# bbc_micro.net
KiCad netlist of a schematic drawn in EAGLE
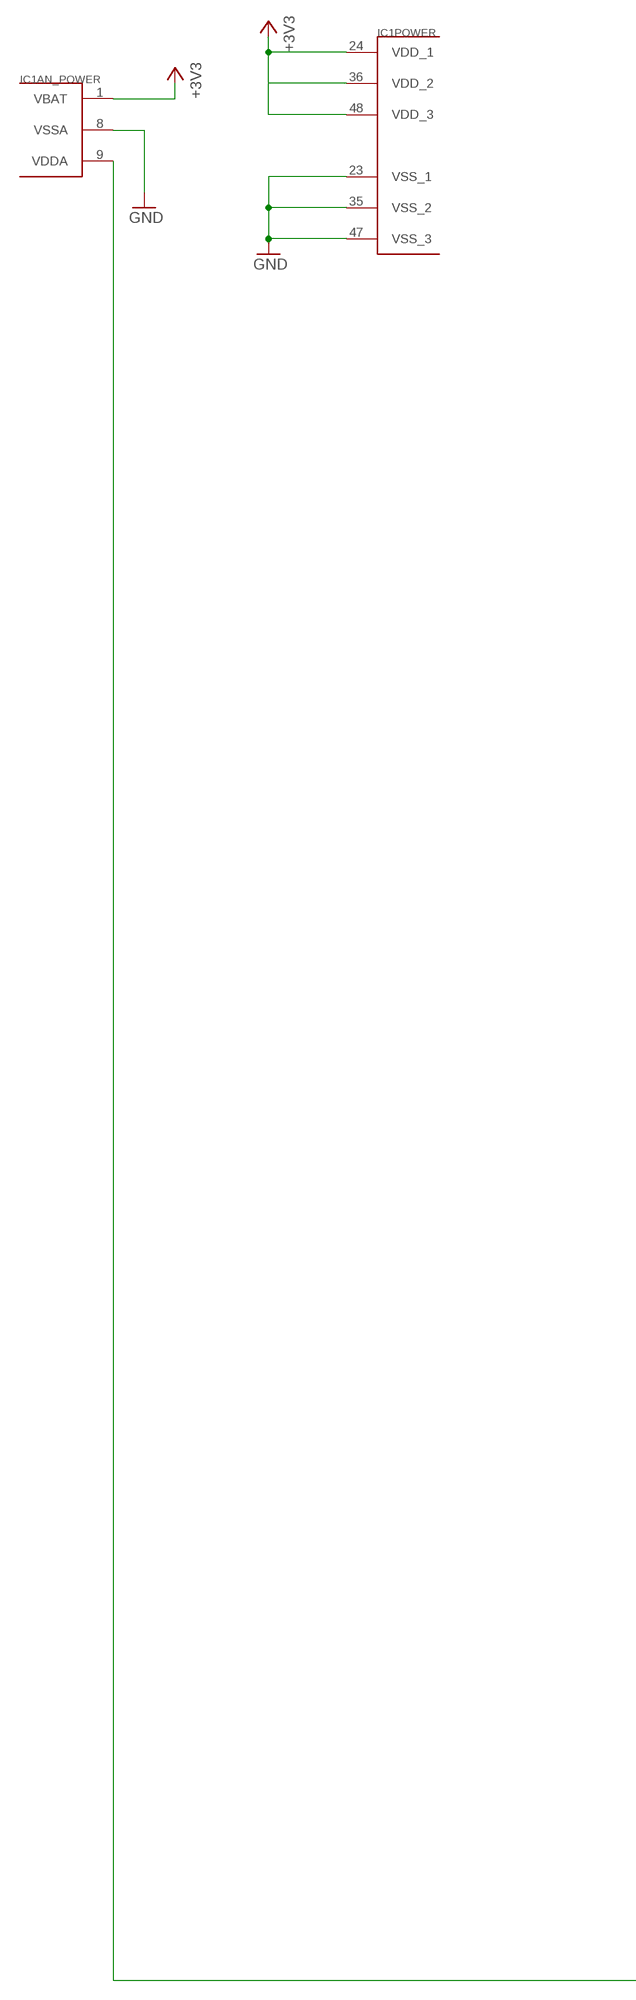
[diagram p0: schematic, sheet 1, part 1 of 2]
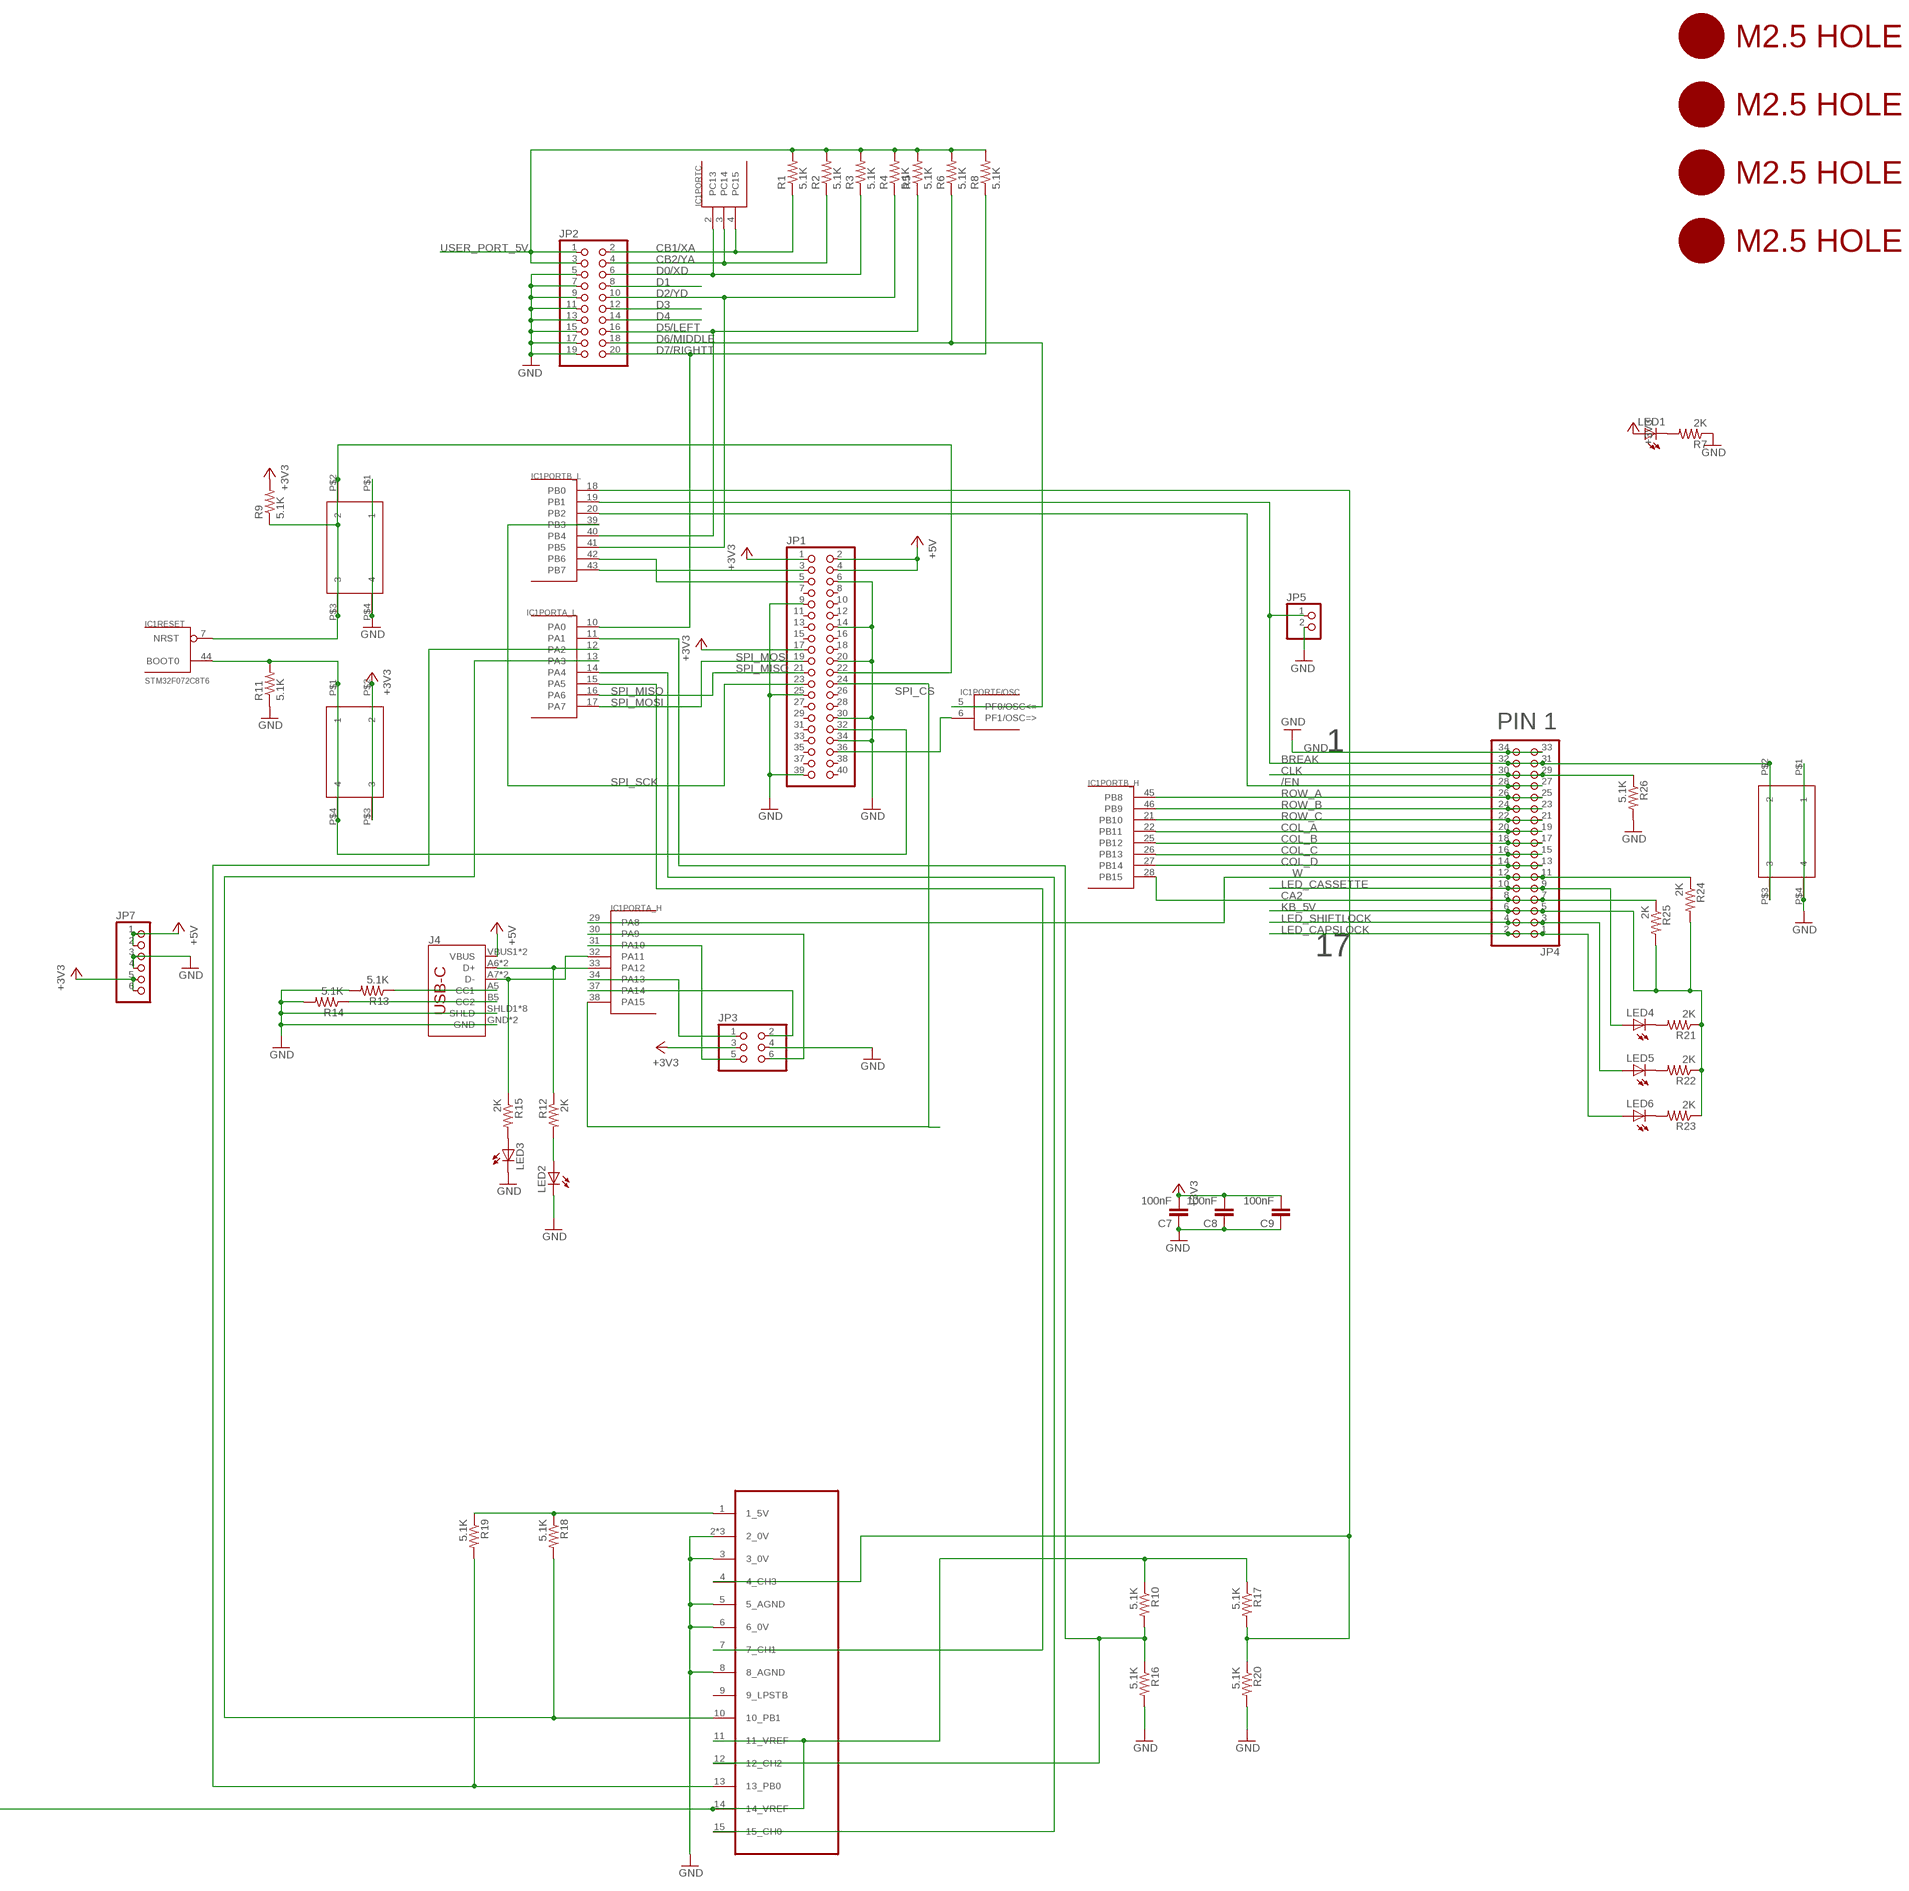
[diagram p1: schematic, sheet 1, part 2 of 2]

(export (version "E")
  (design (tool "Eeschema 10.0.6"))
  (components
    (comp (ref "C7")
      (value "100nF")
      (footprint "eagle-import:0805@1")
      (libsource (lib "eagle-import") (part "CAP0805"))
    )
    (comp (ref "C8")
      (value "100nF")
      (footprint "eagle-import:0805@1")
      (libsource (lib "eagle-import") (part "CAP0805"))
    )
    (comp (ref "C9")
      (value "100nF")
      (footprint "eagle-import:0805@1")
      (libsource (lib "eagle-import") (part "CAP0805"))
    )
    (comp (ref "IC1")
      (value "STM32F072C8T6")
      (footprint "eagle-import:TQFP48")
      (libsource (lib "eagle-import") (part "STM32F072C8T6"))
    )
    (comp (ref "J4")
      (value "USB_C16PIN")
      (footprint "eagle-import:USB-C-16P")
      (libsource (lib "eagle-import") (part "USB_C16PIN"))
    )
    (comp (ref "JP1")
      (value "PINHD-2X20-BIG")
      (footprint "eagle-import:2X20-BIG")
      (libsource (lib "eagle-import") (part "PINHD-2X20-BIG"))
    )
    (comp (ref "JP2")
      (value "PINHD-2X10/90")
      (footprint "eagle-import:2X10_90")
      (libsource (lib "eagle-import") (part "PINHD-2X10/90"))
    )
    (comp (ref "JP3")
      (value "PINHD-2X3")
      (footprint "eagle-import:2X03")
      (libsource (lib "eagle-import") (part "PINHD-2X3"))
    )
    (comp (ref "JP4")
      (value "PINHD-2X17/90")
      (footprint "eagle-import:2X17_90")
      (libsource (lib "eagle-import") (part "PINHD-2X17/90"))
    )
    (comp (ref "JP5")
      (value "PINHD-1X2")
      (footprint "eagle-import:1X02")
      (libsource (lib "eagle-import") (part "PINHD-1X2"))
    )
    (comp (ref "JP7")
      (value "PINHD-1X6CB")
      (footprint "eagle-import:1X06-CLEANBIG")
      (libsource (lib "eagle-import") (part "PINHD-1X6CB"))
    )
    (comp (ref "LED1")
      (value "LEDCHIP-LED0805")
      (footprint "eagle-import:CHIP-LED0805")
      (libsource (lib "eagle-import") (part "LEDCHIP-LED0805"))
    )
    (comp (ref "LED2")
      (value "LEDCHIP-LED0805")
      (footprint "eagle-import:CHIP-LED0805")
      (libsource (lib "eagle-import") (part "LEDCHIP-LED0805"))
    )
    (comp (ref "LED3")
      (value "LEDCHIP-LED0805")
      (footprint "eagle-import:CHIP-LED0805")
      (libsource (lib "eagle-import") (part "LEDCHIP-LED0805"))
    )
    (comp (ref "LED4")
      (value "LEDCHIP-LED0805")
      (footprint "eagle-import:CHIP-LED0805")
      (libsource (lib "eagle-import") (part "LEDCHIP-LED0805"))
    )
    (comp (ref "LED5")
      (value "LEDCHIP-LED0805")
      (footprint "eagle-import:CHIP-LED0805")
      (libsource (lib "eagle-import") (part "LEDCHIP-LED0805"))
    )
    (comp (ref "LED6")
      (value "LEDCHIP-LED0805")
      (footprint "eagle-import:CHIP-LED0805")
      (libsource (lib "eagle-import") (part "LEDCHIP-LED0805"))
    )
    (comp (ref "R1")
      (value "5.1K")
      (footprint "eagle-import:0805")
      (libsource (lib "eagle-import") (part "RESISTOR0805-RES"))
    )
    (comp (ref "R2")
      (value "5.1K")
      (footprint "eagle-import:0805")
      (libsource (lib "eagle-import") (part "RESISTOR0805-RES"))
    )
    (comp (ref "R3")
      (value "5.1K")
      (footprint "eagle-import:0805")
      (libsource (lib "eagle-import") (part "RESISTOR0805-RES"))
    )
    (comp (ref "R4")
      (value "5.1K")
      (footprint "eagle-import:0805")
      (libsource (lib "eagle-import") (part "RESISTOR0805-RES"))
    )
    (comp (ref "R5")
      (value "5.1K")
      (footprint "eagle-import:0805")
      (libsource (lib "eagle-import") (part "RESISTOR0805-RES"))
    )
    (comp (ref "R6")
      (value "5.1K")
      (footprint "eagle-import:0805")
      (libsource (lib "eagle-import") (part "RESISTOR0805-RES"))
    )
    (comp (ref "R7")
      (value "2K")
      (footprint "eagle-import:0805")
      (libsource (lib "eagle-import") (part "RESISTOR0805-RES"))
    )
    (comp (ref "R8")
      (value "5.1K")
      (footprint "eagle-import:0805")
      (libsource (lib "eagle-import") (part "RESISTOR0805-RES"))
    )
    (comp (ref "R9")
      (value "5.1K")
      (footprint "eagle-import:0805")
      (libsource (lib "eagle-import") (part "RESISTOR0805-RES"))
    )
    (comp (ref "R10")
      (value "5.1K")
      (footprint "eagle-import:0805")
      (libsource (lib "eagle-import") (part "RESISTOR0805-RES"))
    )
    (comp (ref "R11")
      (value "5.1K")
      (footprint "eagle-import:0805")
      (libsource (lib "eagle-import") (part "RESISTOR0805-RES"))
    )
    (comp (ref "R12")
      (value "2K")
      (footprint "eagle-import:0805")
      (libsource (lib "eagle-import") (part "RESISTOR0805-RES"))
    )
    (comp (ref "R13")
      (value "5.1K")
      (footprint "eagle-import:0805")
      (libsource (lib "eagle-import") (part "RESISTOR0805-RES"))
    )
    (comp (ref "R14")
      (value "5.1K")
      (footprint "eagle-import:0805")
      (libsource (lib "eagle-import") (part "RESISTOR0805-RES"))
    )
    (comp (ref "R15")
      (value "2K")
      (footprint "eagle-import:0805")
      (libsource (lib "eagle-import") (part "RESISTOR0805-RES"))
    )
    (comp (ref "R16")
      (value "5.1K")
      (footprint "eagle-import:0805")
      (libsource (lib "eagle-import") (part "RESISTOR0805-RES"))
    )
    (comp (ref "R17")
      (value "5.1K")
      (footprint "eagle-import:0805")
      (libsource (lib "eagle-import") (part "RESISTOR0805-RES"))
    )
    (comp (ref "R18")
      (value "5.1K")
      (footprint "eagle-import:0805")
      (libsource (lib "eagle-import") (part "RESISTOR0805-RES"))
    )
    (comp (ref "R19")
      (value "5.1K")
      (footprint "eagle-import:0805")
      (libsource (lib "eagle-import") (part "RESISTOR0805-RES"))
    )
    (comp (ref "R20")
      (value "5.1K")
      (footprint "eagle-import:0805")
      (libsource (lib "eagle-import") (part "RESISTOR0805-RES"))
    )
    (comp (ref "R21")
      (value "2K")
      (footprint "eagle-import:0805")
      (libsource (lib "eagle-import") (part "RESISTOR0805-RES"))
    )
    (comp (ref "R22")
      (value "2K")
      (footprint "eagle-import:0805")
      (libsource (lib "eagle-import") (part "RESISTOR0805-RES"))
    )
    (comp (ref "R23")
      (value "2K")
      (footprint "eagle-import:0805")
      (libsource (lib "eagle-import") (part "RESISTOR0805-RES"))
    )
    (comp (ref "R24")
      (value "2K")
      (footprint "eagle-import:0805")
      (libsource (lib "eagle-import") (part "RESISTOR0805-RES"))
    )
    (comp (ref "R25")
      (value "2K")
      (footprint "eagle-import:0805")
      (libsource (lib "eagle-import") (part "RESISTOR0805-RES"))
    )
    (comp (ref "R26")
      (value "5.1K")
      (footprint "eagle-import:0805")
      (libsource (lib "eagle-import") (part "RESISTOR0805-RES"))
    )
    (comp (ref "SW1")
      (value "324_SW")
      (footprint "eagle-import:342_SWICH_FOOT")
      (libsource (lib "eagle-import") (part "324_SW"))
    )
    (comp (ref "SW2")
      (value "324_SW")
      (footprint "eagle-import:342_SWICH_FOOT")
      (libsource (lib "eagle-import") (part "324_SW"))
    )
    (comp (ref "SW3")
      (value "324_SW")
      (footprint "eagle-import:342_SWICH_FOOT")
      (libsource (lib "eagle-import") (part "324_SW"))
    )
    (comp (ref "U$2")
      (value "M2.5HOLE")
      (footprint "eagle-import:M2.5HOLE")
      (libsource (lib "eagle-import") (part "M2.5HOLE"))
    )
    (comp (ref "U$3")
      (value "M2.5HOLE")
      (footprint "eagle-import:M2.5HOLE")
      (libsource (lib "eagle-import") (part "M2.5HOLE"))
    )
    (comp (ref "U$6")
      (value "M2.5HOLE")
      (footprint "eagle-import:M2.5HOLE")
      (libsource (lib "eagle-import") (part "M2.5HOLE"))
    )
    (comp (ref "U$7")
      (value "M2.5HOLE")
      (footprint "eagle-import:M2.5HOLE")
      (libsource (lib "eagle-import") (part "M2.5HOLE"))
    )
    (comp (ref "U$9")
      (value "BBC_15P")
      (footprint "eagle-import:DA15")
      (libsource (lib "eagle-import") (part "BBC_15P"))
    )
  )
  (nets
    (net (code "1") (name "+3V3") (class "Default")
      (node (ref "C7") (pin "2") (pinfunction "2_2") (pintype "passive"))
      (node (ref "C8") (pin "2") (pinfunction "2_2") (pintype "passive"))
      (node (ref "C9") (pin "2") (pinfunction "2_2") (pintype "passive"))
      (node (ref "IC1") (pin "1") (pinfunction "VBAT_1") (pintype "power_in"))
      (node (ref "IC1") (pin "24") (pinfunction "VDD_1_24") (pintype "power_in"))
      (node (ref "IC1") (pin "36") (pinfunction "VDD_2_36") (pintype "power_in"))
      (node (ref "IC1") (pin "48") (pinfunction "VDD_3_48") (pintype "power_in"))
      (node (ref "JP1") (pin "1") (pinfunction "1_1") (pintype "passive"))
      (node (ref "JP1") (pin "17") (pinfunction "17_17") (pintype "passive"))
      (node (ref "JP3") (pin "3") (pinfunction "3_3") (pintype "passive"))
      (node (ref "JP7") (pin "5") (pinfunction "5_5") (pintype "passive"))
      (node (ref "JP7") (pin "6") (pinfunction "6_6") (pintype "passive"))
      (node (ref "LED1") (pin "A") (pinfunction "A_A") (pintype "passive"))
      (node (ref "R9") (pin "2") (pinfunction "2_2") (pintype "passive"))
      (node (ref "SW2") (pin "P$2") (pinfunction "2_P$2") (pintype "bidirectional"))
      (node (ref "SW2") (pin "P$3") (pinfunction "3_P$3") (pintype "bidirectional"))
    )
    (net (code "2") (name "+5V") (class "Default")
      (node (ref "J4") (pin "VBUS1") (pinfunction "VBUS_VBUS1") (pintype "bidirectional"))
      (node (ref "J4") (pin "VBUS2") (pinfunction "VBUS_VBUS2") (pintype "bidirectional"))
      (node (ref "JP1") (pin "2") (pinfunction "2_2") (pintype "passive"))
      (node (ref "JP1") (pin "4") (pinfunction "4_4") (pintype "passive"))
      (node (ref "JP7") (pin "1") (pinfunction "1_1") (pintype "passive"))
      (node (ref "JP7") (pin "2") (pinfunction "2_2") (pintype "passive"))
    )
    (net (code "3") (name "/BREAK") (class "Default")
      (node (ref "IC1") (pin "19") (pinfunction "PB1_19") (pintype "bidirectional"))
      (node (ref "JP4") (pin "31") (pinfunction "31_31") (pintype "passive"))
      (node (ref "JP4") (pin "32") (pinfunction "32_32") (pintype "passive"))
      (node (ref "JP5") (pin "1") (pinfunction "1_1") (pintype "passive"))
      (node (ref "SW3") (pin "P$2") (pinfunction "2_P$2") (pintype "bidirectional"))
      (node (ref "SW3") (pin "P$3") (pinfunction "3_P$3") (pintype "bidirectional"))
    )
    (net (code "4") (name "/CA2") (class "Default")
      (node (ref "IC1") (pin "28") (pinfunction "PB15_28") (pintype "bidirectional"))
      (node (ref "JP4") (pin "7") (pinfunction "7_7") (pintype "passive"))
      (node (ref "JP4") (pin "8") (pinfunction "8_8") (pintype "passive"))
      (node (ref "R25") (pin "1") (pinfunction "1_1") (pintype "passive"))
    )
    (net (code "5") (name "/CB1{slash}XA") (class "Default")
      (node (ref "IC1") (pin "4") (pinfunction "PC15_4") (pintype "bidirectional"))
      (node (ref "JP2") (pin "2") (pinfunction "2_2") (pintype "passive"))
      (node (ref "R1") (pin "1") (pinfunction "1_1") (pintype "passive"))
    )
    (net (code "6") (name "/CB2{slash}YA") (class "Default")
      (node (ref "IC1") (pin "3") (pinfunction "PC14_3") (pintype "bidirectional"))
      (node (ref "JP2") (pin "4") (pinfunction "4_4") (pintype "passive"))
      (node (ref "R2") (pin "1") (pinfunction "1_1") (pintype "passive"))
    )
    (net (code "7") (name "/CLK") (class "Default")
      (node (ref "JP4") (pin "29") (pinfunction "29_29") (pintype "passive"))
      (node (ref "JP4") (pin "30") (pinfunction "30_30") (pintype "passive"))
      (node (ref "R26") (pin "1") (pinfunction "1_1") (pintype "passive"))
    )
    (net (code "8") (name "/COL_A") (class "Default")
      (node (ref "IC1") (pin "22") (pinfunction "PB11_22") (pintype "bidirectional"))
      (node (ref "JP4") (pin "19") (pinfunction "19_19") (pintype "passive"))
      (node (ref "JP4") (pin "20") (pinfunction "20_20") (pintype "passive"))
    )
    (net (code "9") (name "/COL_B") (class "Default")
      (node (ref "IC1") (pin "25") (pinfunction "PB12_25") (pintype "bidirectional"))
      (node (ref "JP4") (pin "17") (pinfunction "17_17") (pintype "passive"))
      (node (ref "JP4") (pin "18") (pinfunction "18_18") (pintype "passive"))
    )
    (net (code "10") (name "/COL_C") (class "Default")
      (node (ref "IC1") (pin "26") (pinfunction "PB13_26") (pintype "bidirectional"))
      (node (ref "JP4") (pin "15") (pinfunction "15_15") (pintype "passive"))
      (node (ref "JP4") (pin "16") (pinfunction "16_16") (pintype "passive"))
    )
    (net (code "11") (name "/COL_D") (class "Default")
      (node (ref "IC1") (pin "27") (pinfunction "PB14_27") (pintype "bidirectional"))
      (node (ref "JP4") (pin "13") (pinfunction "13_13") (pintype "passive"))
      (node (ref "JP4") (pin "14") (pinfunction "14_14") (pintype "passive"))
    )
    (net (code "12") (name "/D0{slash}XD") (class "Default")
      (node (ref "IC1") (pin "2") (pinfunction "PC13_2") (pintype "bidirectional"))
      (node (ref "JP2") (pin "6") (pinfunction "6_6") (pintype "passive"))
      (node (ref "R3") (pin "1") (pinfunction "1_1") (pintype "passive"))
    )
    (net (code "13") (name "/D1") (class "Default")
      (node (ref "JP2") (pin "8") (pinfunction "8_8") (pintype "passive"))
    )
    (net (code "14") (name "/D2{slash}YD") (class "Default")
      (node (ref "IC1") (pin "41") (pinfunction "PB5_41") (pintype "bidirectional"))
      (node (ref "JP2") (pin "10") (pinfunction "10_10") (pintype "passive"))
      (node (ref "R4") (pin "1") (pinfunction "1_1") (pintype "passive"))
    )
    (net (code "15") (name "/D3") (class "Default")
      (node (ref "JP2") (pin "12") (pinfunction "12_12") (pintype "passive"))
    )
    (net (code "16") (name "/D4") (class "Default")
      (node (ref "JP2") (pin "14") (pinfunction "14_14") (pintype "passive"))
    )
    (net (code "17") (name "/D5{slash}LEFT") (class "Default")
      (node (ref "IC1") (pin "40") (pinfunction "PB4_40") (pintype "bidirectional"))
      (node (ref "JP2") (pin "16") (pinfunction "16_16") (pintype "passive"))
      (node (ref "R5") (pin "1") (pinfunction "1_1") (pintype "passive"))
    )
    (net (code "18") (name "/D6{slash}MIDDLE") (class "Default")
      (node (ref "IC1") (pin "5") (pinfunction "PF0/OSC<=_5") (pintype "bidirectional"))
      (node (ref "JP2") (pin "18") (pinfunction "18_18") (pintype "passive"))
      (node (ref "R6") (pin "1") (pinfunction "1_1") (pintype "passive"))
    )
    (net (code "19") (name "/D7{slash}RIGHTT") (class "Default")
      (node (ref "IC1") (pin "10") (pinfunction "PA0_10") (pintype "bidirectional"))
      (node (ref "JP2") (pin "20") (pinfunction "20_20") (pintype "passive"))
      (node (ref "R8") (pin "1") (pinfunction "1_1") (pintype "passive"))
    )
    (net (code "20") (name "/KB_5V") (class "Default")
      (node (ref "JP4") (pin "5") (pinfunction "5_5") (pintype "passive"))
      (node (ref "JP4") (pin "6") (pinfunction "6_6") (pintype "passive"))
      (node (ref "R21") (pin "1") (pinfunction "1_1") (pintype "passive"))
      (node (ref "R22") (pin "1") (pinfunction "1_1") (pintype "passive"))
      (node (ref "R23") (pin "1") (pinfunction "1_1") (pintype "passive"))
      (node (ref "R24") (pin "2") (pinfunction "2_2") (pintype "passive"))
      (node (ref "R25") (pin "2") (pinfunction "2_2") (pintype "passive"))
    )
    (net (code "21") (name "/LED_CAPSLOCK") (class "Default")
      (node (ref "JP4") (pin "1") (pinfunction "1_1") (pintype "passive"))
      (node (ref "JP4") (pin "2") (pinfunction "2_2") (pintype "passive"))
      (node (ref "LED6") (pin "A") (pinfunction "A_A") (pintype "passive"))
    )
    (net (code "22") (name "/LED_CASSETTE") (class "Default")
      (node (ref "JP4") (pin "10") (pinfunction "10_10") (pintype "passive"))
      (node (ref "JP4") (pin "9") (pinfunction "9_9") (pintype "passive"))
      (node (ref "LED4") (pin "A") (pinfunction "A_A") (pintype "passive"))
    )
    (net (code "23") (name "/LED_SHIFTLOCK") (class "Default")
      (node (ref "JP4") (pin "3") (pinfunction "3_3") (pintype "passive"))
      (node (ref "JP4") (pin "4") (pinfunction "4_4") (pintype "passive"))
      (node (ref "LED5") (pin "A") (pinfunction "A_A") (pintype "passive"))
    )
    (net (code "24") (name "/ROW_A") (class "Default")
      (node (ref "IC1") (pin "45") (pinfunction "PB8_45") (pintype "bidirectional"))
      (node (ref "JP4") (pin "25") (pinfunction "25_25") (pintype "passive"))
      (node (ref "JP4") (pin "26") (pinfunction "26_26") (pintype "passive"))
    )
    (net (code "25") (name "/ROW_B") (class "Default")
      (node (ref "IC1") (pin "46") (pinfunction "PB9_46") (pintype "bidirectional"))
      (node (ref "JP4") (pin "23") (pinfunction "23_23") (pintype "passive"))
      (node (ref "JP4") (pin "24") (pinfunction "24_24") (pintype "passive"))
    )
    (net (code "26") (name "/ROW_C") (class "Default")
      (node (ref "IC1") (pin "21") (pinfunction "PB10_21") (pintype "bidirectional"))
      (node (ref "JP4") (pin "21") (pinfunction "21_21") (pintype "passive"))
      (node (ref "JP4") (pin "22") (pinfunction "22_22") (pintype "passive"))
    )
    (net (code "27") (name "/SPI_CS") (class "Default")
      (node (ref "IC1") (pin "38") (pinfunction "PA15_38") (pintype "bidirectional"))
      (node (ref "JP1") (pin "24") (pinfunction "24_24") (pintype "passive"))
    )
    (net (code "28") (name "/SPI_MISO") (class "Default")
      (node (ref "IC1") (pin "16") (pinfunction "PA6_16") (pintype "bidirectional"))
      (node (ref "JP1") (pin "21") (pinfunction "21_21") (pintype "passive"))
    )
    (net (code "29") (name "/SPI_MOSI") (class "Default")
      (node (ref "IC1") (pin "17") (pinfunction "PA7_17") (pintype "bidirectional"))
      (node (ref "JP1") (pin "19") (pinfunction "19_19") (pintype "passive"))
    )
    (net (code "30") (name "/SPI_SCK") (class "Default")
      (node (ref "IC1") (pin "39") (pinfunction "PB3_39") (pintype "bidirectional"))
      (node (ref "JP1") (pin "23") (pinfunction "23_23") (pintype "passive"))
    )
    (net (code "31") (name "/USER_PORT_5V") (class "Default")
      (node (ref "JP2") (pin "1") (pinfunction "1_1") (pintype "passive"))
      (node (ref "JP2") (pin "3") (pinfunction "3_3") (pintype "passive"))
      (node (ref "R1") (pin "2") (pinfunction "2_2") (pintype "passive"))
      (node (ref "R2") (pin "2") (pinfunction "2_2") (pintype "passive"))
      (node (ref "R3") (pin "2") (pinfunction "2_2") (pintype "passive"))
      (node (ref "R4") (pin "2") (pinfunction "2_2") (pintype "passive"))
      (node (ref "R5") (pin "2") (pinfunction "2_2") (pintype "passive"))
      (node (ref "R6") (pin "2") (pinfunction "2_2") (pintype "passive"))
      (node (ref "R8") (pin "2") (pinfunction "2_2") (pintype "passive"))
    )
    (net (code "32") (name "/W") (class "Default")
      (node (ref "IC1") (pin "29") (pinfunction "PA8_29") (pintype "bidirectional"))
      (node (ref "JP4") (pin "11") (pinfunction "11_11") (pintype "passive"))
      (node (ref "JP4") (pin "12") (pinfunction "12_12") (pintype "passive"))
      (node (ref "R24") (pin "1") (pinfunction "1_1") (pintype "passive"))
    )
    (net (code "33") (name "/{slash}EN") (class "Default")
      (node (ref "IC1") (pin "20") (pinfunction "PB2_20") (pintype "bidirectional"))
      (node (ref "JP4") (pin "27") (pinfunction "27_27") (pintype "passive"))
      (node (ref "JP4") (pin "28") (pinfunction "28_28") (pintype "passive"))
    )
    (net (code "34") (name "GND") (class "Default")
      (node (ref "C7") (pin "1") (pinfunction "1_1") (pintype "passive"))
      (node (ref "C8") (pin "1") (pinfunction "1_1") (pintype "passive"))
      (node (ref "C9") (pin "1") (pinfunction "1_1") (pintype "passive"))
      (node (ref "IC1") (pin "23") (pinfunction "VSS_1_23") (pintype "power_in"))
      (node (ref "IC1") (pin "35") (pinfunction "VSS_2_35") (pintype "power_in"))
      (node (ref "IC1") (pin "47") (pinfunction "VSS_3_47") (pintype "power_in"))
      (node (ref "IC1") (pin "8") (pinfunction "VSSA_8") (pintype "power_in"))
      (node (ref "J4") (pin "GND") (pinfunction "GND_GND") (pintype "bidirectional"))
      (node (ref "J4") (pin "GND2") (pinfunction "GND_GND2") (pintype "bidirectional"))
      (node (ref "J4") (pin "SHLD1") (pinfunction "SHLD_SHLD1") (pintype "bidirectional"))
      (node (ref "J4") (pin "SHLD2") (pinfunction "SHLD_SHLD2") (pintype "bidirectional"))
      (node (ref "J4") (pin "SHLD3") (pinfunction "SHLD_SHLD3") (pintype "bidirectional"))
      (node (ref "J4") (pin "SHLD4") (pinfunction "SHLD_SHLD4") (pintype "bidirectional"))
      (node (ref "J4") (pin "SHLD5") (pinfunction "SHLD_SHLD5") (pintype "bidirectional"))
      (node (ref "J4") (pin "SHLD6") (pinfunction "SHLD_SHLD6") (pintype "bidirectional"))
      (node (ref "J4") (pin "SHLD7") (pinfunction "SHLD_SHLD7") (pintype "bidirectional"))
      (node (ref "J4") (pin "SHLD8") (pinfunction "SHLD_SHLD8") (pintype "bidirectional"))
      (node (ref "JP1") (pin "14") (pinfunction "14_14") (pintype "passive"))
      (node (ref "JP1") (pin "20") (pinfunction "20_20") (pintype "passive"))
      (node (ref "JP1") (pin "25") (pinfunction "25_25") (pintype "passive"))
      (node (ref "JP1") (pin "30") (pinfunction "30_30") (pintype "passive"))
      (node (ref "JP1") (pin "34") (pinfunction "34_34") (pintype "passive"))
      (node (ref "JP1") (pin "39") (pinfunction "39_39") (pintype "passive"))
      (node (ref "JP1") (pin "6") (pinfunction "6_6") (pintype "passive"))
      (node (ref "JP1") (pin "9") (pinfunction "9_9") (pintype "passive"))
      (node (ref "JP2") (pin "11") (pinfunction "11_11") (pintype "passive"))
      (node (ref "JP2") (pin "13") (pinfunction "13_13") (pintype "passive"))
      (node (ref "JP2") (pin "15") (pinfunction "15_15") (pintype "passive"))
      (node (ref "JP2") (pin "17") (pinfunction "17_17") (pintype "passive"))
      (node (ref "JP2") (pin "19") (pinfunction "19_19") (pintype "passive"))
      (node (ref "JP2") (pin "5") (pinfunction "5_5") (pintype "passive"))
      (node (ref "JP2") (pin "7") (pinfunction "7_7") (pintype "passive"))
      (node (ref "JP2") (pin "9") (pinfunction "9_9") (pintype "passive"))
      (node (ref "JP3") (pin "4") (pinfunction "4_4") (pintype "passive"))
      (node (ref "JP4") (pin "33") (pinfunction "33_33") (pintype "passive"))
      (node (ref "JP4") (pin "34") (pinfunction "34_34") (pintype "passive"))
      (node (ref "JP5") (pin "2") (pinfunction "2_2") (pintype "passive"))
      (node (ref "JP7") (pin "3") (pinfunction "3_3") (pintype "passive"))
      (node (ref "JP7") (pin "4") (pinfunction "4_4") (pintype "passive"))
      (node (ref "LED2") (pin "C") (pinfunction "C_C") (pintype "passive"))
      (node (ref "LED3") (pin "C") (pinfunction "C_C") (pintype "passive"))
      (node (ref "R11") (pin "1") (pinfunction "1_1") (pintype "passive"))
      (node (ref "R13") (pin "2") (pinfunction "2_2") (pintype "passive"))
      (node (ref "R14") (pin "2") (pinfunction "2_2") (pintype "passive"))
      (node (ref "R16") (pin "2") (pinfunction "2_2") (pintype "passive"))
      (node (ref "R20") (pin "2") (pinfunction "2_2") (pintype "passive"))
      (node (ref "R26") (pin "2") (pinfunction "2_2") (pintype "passive"))
      (node (ref "R7") (pin "1") (pinfunction "1_1") (pintype "passive"))
      (node (ref "SW1") (pin "P$1") (pinfunction "1_P$1") (pintype "bidirectional"))
      (node (ref "SW1") (pin "P$4") (pinfunction "4_P$4") (pintype "bidirectional"))
      (node (ref "SW3") (pin "P$1") (pinfunction "1_P$1") (pintype "bidirectional"))
      (node (ref "SW3") (pin "P$4") (pinfunction "4_P$4") (pintype "bidirectional"))
      (node (ref "U$9") (pin "2") (pinfunction "2_0V_2") (pintype "bidirectional"))
      (node (ref "U$9") (pin "3") (pinfunction "3_0V_3") (pintype "bidirectional"))
      (node (ref "U$9") (pin "5") (pinfunction "5_AGND_5") (pintype "bidirectional"))
      (node (ref "U$9") (pin "6") (pinfunction "6_0V_6") (pintype "bidirectional"))
      (node (ref "U$9") (pin "8") (pinfunction "8_AGND_8") (pintype "bidirectional"))
      (node (ref "U$9") (pin "G1") (pinfunction "2_0V_G1") (pintype "bidirectional"))
      (node (ref "U$9") (pin "G2") (pinfunction "2_0V_G2") (pintype "bidirectional"))
    )
    (net (code "35") (name "Net-(IC1A-VDDA)") (class "Default")
      (node (ref "IC1") (pin "9") (pinfunction "VDDA_9") (pintype "power_in"))
      (node (ref "R10") (pin "1") (pinfunction "1_1") (pintype "passive"))
      (node (ref "R17") (pin "1") (pinfunction "1_1") (pintype "passive"))
      (node (ref "U$9") (pin "11") (pinfunction "11_VREF_11") (pintype "bidirectional"))
      (node (ref "U$9") (pin "14") (pinfunction "14_VREF_14") (pintype "bidirectional"))
    )
    (net (code "36") (name "Net-(IC1B-PA9)") (class "Default")
      (node (ref "IC1") (pin "30") (pinfunction "PA9_30") (pintype "bidirectional"))
      (node (ref "JP3") (pin "6") (pinfunction "6_6") (pintype "passive"))
    )
    (net (code "37") (name "Net-(IC1B-PA10)") (class "Default")
      (node (ref "IC1") (pin "31") (pinfunction "PA10_31") (pintype "bidirectional"))
      (node (ref "JP3") (pin "5") (pinfunction "5_5") (pintype "passive"))
    )
    (net (code "38") (name "Net-(IC1B-PA11)") (class "Default")
      (node (ref "IC1") (pin "32") (pinfunction "PA11_32") (pintype "bidirectional"))
      (node (ref "J4") (pin "A7") (pinfunction "D-_A7") (pintype "bidirectional"))
      (node (ref "J4") (pin "B7") (pinfunction "D-_B7") (pintype "bidirectional"))
      (node (ref "R15") (pin "1") (pinfunction "1_1") (pintype "passive"))
    )
    (net (code "39") (name "Net-(IC1B-PA12)") (class "Default")
      (node (ref "IC1") (pin "33") (pinfunction "PA12_33") (pintype "bidirectional"))
      (node (ref "J4") (pin "A6") (pinfunction "D+_A6") (pintype "bidirectional"))
      (node (ref "J4") (pin "B6") (pinfunction "D+_B6") (pintype "bidirectional"))
      (node (ref "R12") (pin "1") (pinfunction "1_1") (pintype "passive"))
    )
    (net (code "40") (name "Net-(IC1B-PA13)") (class "Default")
      (node (ref "IC1") (pin "34") (pinfunction "PA13_34") (pintype "bidirectional"))
      (node (ref "JP3") (pin "1") (pinfunction "1_1") (pintype "passive"))
    )
    (net (code "41") (name "Net-(IC1B-PA14)") (class "Default")
      (node (ref "IC1") (pin "37") (pinfunction "PA14_37") (pintype "bidirectional"))
      (node (ref "JP3") (pin "2") (pinfunction "2_2") (pintype "passive"))
    )
    (net (code "42") (name "Net-(IC1C-PA1)") (class "Default")
      (node (ref "IC1") (pin "11") (pinfunction "PA1_11") (pintype "bidirectional"))
      (node (ref "R10") (pin "2") (pinfunction "2_2") (pintype "passive"))
      (node (ref "R16") (pin "1") (pinfunction "1_1") (pintype "passive"))
      (node (ref "U$9") (pin "12") (pinfunction "12_CH2_12") (pintype "bidirectional"))
    )
    (net (code "43") (name "Net-(IC1C-PA2)") (class "Default")
      (node (ref "IC1") (pin "12") (pinfunction "PA2_12") (pintype "bidirectional"))
      (node (ref "R19") (pin "2") (pinfunction "2_2") (pintype "passive"))
      (node (ref "U$9") (pin "13") (pinfunction "13_PB0_13") (pintype "bidirectional"))
    )
    (net (code "44") (name "Net-(IC1C-PA3)") (class "Default")
      (node (ref "IC1") (pin "13") (pinfunction "PA3_13") (pintype "bidirectional"))
      (node (ref "R18") (pin "2") (pinfunction "2_2") (pintype "passive"))
      (node (ref "U$9") (pin "10") (pinfunction "10_PB1_10") (pintype "bidirectional"))
    )
    (net (code "45") (name "Net-(IC1C-PA4)") (class "Default")
      (node (ref "IC1") (pin "14") (pinfunction "PA4_14") (pintype "bidirectional"))
      (node (ref "U$9") (pin "15") (pinfunction "15_CH0_15") (pintype "bidirectional"))
    )
    (net (code "46") (name "Net-(IC1C-PA5)") (class "Default")
      (node (ref "IC1") (pin "15") (pinfunction "PA5_15") (pintype "bidirectional"))
      (node (ref "U$9") (pin "7") (pinfunction "7_CH1_7") (pintype "bidirectional"))
    )
    (net (code "47") (name "Net-(IC1E-PB0)") (class "Default")
      (node (ref "IC1") (pin "18") (pinfunction "PB0_18") (pintype "bidirectional"))
      (node (ref "R17") (pin "2") (pinfunction "2_2") (pintype "passive"))
      (node (ref "R20") (pin "1") (pinfunction "1_1") (pintype "passive"))
      (node (ref "U$9") (pin "4") (pinfunction "4_CH3_4") (pintype "bidirectional"))
    )
    (net (code "48") (name "Net-(IC1E-PB6)") (class "Default")
      (node (ref "IC1") (pin "42") (pinfunction "PB6_42") (pintype "bidirectional"))
      (node (ref "JP1") (pin "5") (pinfunction "5_5") (pintype "passive"))
    )
    (net (code "49") (name "Net-(IC1E-PB7)") (class "Default")
      (node (ref "IC1") (pin "43") (pinfunction "PB7_43") (pintype "bidirectional"))
      (node (ref "JP1") (pin "3") (pinfunction "3_3") (pintype "passive"))
    )
    (net (code "50") (name "Net-(IC1G-PF1{slash}OSC=>)") (class "Default")
      (node (ref "IC1") (pin "6") (pinfunction "PF1/OSC=>_6") (pintype "bidirectional"))
      (node (ref "JP1") (pin "36") (pinfunction "36_36") (pintype "passive"))
    )
    (net (code "51") (name "Net-(IC1I-BOOT0)") (class "Default")
      (node (ref "IC1") (pin "44") (pinfunction "BOOT0_44") (pintype "input"))
      (node (ref "JP1") (pin "32") (pinfunction "32_32") (pintype "passive"))
      (node (ref "R11") (pin "2") (pinfunction "2_2") (pintype "passive"))
      (node (ref "SW2") (pin "P$1") (pinfunction "1_P$1") (pintype "bidirectional"))
      (node (ref "SW2") (pin "P$4") (pinfunction "4_P$4") (pintype "bidirectional"))
    )
    (net (code "52") (name "Net-(IC1I-NRST)") (class "Default")
      (node (ref "IC1") (pin "7") (pinfunction "NRST_7") (pintype "input"))
      (node (ref "JP1") (pin "22") (pinfunction "22_22") (pintype "passive"))
      (node (ref "R9") (pin "1") (pinfunction "1_1") (pintype "passive"))
      (node (ref "SW1") (pin "P$2") (pinfunction "2_P$2") (pintype "bidirectional"))
      (node (ref "SW1") (pin "P$3") (pinfunction "3_P$3") (pintype "bidirectional"))
    )
    (net (code "53") (name "Net-(J4-CC1)") (class "Default")
      (node (ref "J4") (pin "A5") (pinfunction "CC1_A5") (pintype "bidirectional"))
      (node (ref "R13") (pin "1") (pinfunction "1_1") (pintype "passive"))
    )
    (net (code "54") (name "Net-(J4-CC2)") (class "Default")
      (node (ref "J4") (pin "B5") (pinfunction "CC2_B5") (pintype "bidirectional"))
      (node (ref "R14") (pin "1") (pinfunction "1_1") (pintype "passive"))
    )
    (net (code "55") (name "Net-(LED1-PadC)") (class "Default")
      (node (ref "LED1") (pin "C") (pinfunction "C_C") (pintype "passive"))
      (node (ref "R7") (pin "2") (pinfunction "2_2") (pintype "passive"))
    )
    (net (code "56") (name "Net-(LED2-PadA)") (class "Default")
      (node (ref "LED2") (pin "A") (pinfunction "A_A") (pintype "passive"))
      (node (ref "R12") (pin "2") (pinfunction "2_2") (pintype "passive"))
    )
    (net (code "57") (name "Net-(LED3-PadA)") (class "Default")
      (node (ref "LED3") (pin "A") (pinfunction "A_A") (pintype "passive"))
      (node (ref "R15") (pin "2") (pinfunction "2_2") (pintype "passive"))
    )
    (net (code "58") (name "Net-(LED4-PadC)") (class "Default")
      (node (ref "LED4") (pin "C") (pinfunction "C_C") (pintype "passive"))
      (node (ref "R21") (pin "2") (pinfunction "2_2") (pintype "passive"))
    )
    (net (code "59") (name "Net-(LED5-PadC)") (class "Default")
      (node (ref "LED5") (pin "C") (pinfunction "C_C") (pintype "passive"))
      (node (ref "R22") (pin "2") (pinfunction "2_2") (pintype "passive"))
    )
    (net (code "60") (name "Net-(LED6-PadC)") (class "Default")
      (node (ref "LED6") (pin "C") (pinfunction "C_C") (pintype "passive"))
      (node (ref "R23") (pin "2") (pinfunction "2_2") (pintype "passive"))
    )
    (net (code "61") (name "Net-(U$9-1_5V)") (class "Default")
      (node (ref "R18") (pin "1") (pinfunction "1_1") (pintype "passive"))
      (node (ref "R19") (pin "1") (pinfunction "1_1") (pintype "passive"))
      (node (ref "U$9") (pin "1") (pinfunction "1_5V_1") (pintype "bidirectional"))
    )
    (net (code "62") (name "unconnected-(JP1-Pad7)") (class "Default")
      (node (ref "JP1") (pin "7") (pinfunction "7_7") (pintype "passive"))
    )
    (net (code "63") (name "unconnected-(JP1-Pad8)") (class "Default")
      (node (ref "JP1") (pin "8") (pinfunction "8_8") (pintype "passive"))
    )
    (net (code "64") (name "unconnected-(JP1-Pad10)") (class "Default")
      (node (ref "JP1") (pin "10") (pinfunction "10_10") (pintype "passive"))
    )
    (net (code "65") (name "unconnected-(JP1-Pad11)") (class "Default")
      (node (ref "JP1") (pin "11") (pinfunction "11_11") (pintype "passive"))
    )
    (net (code "66") (name "unconnected-(JP1-Pad12)") (class "Default")
      (node (ref "JP1") (pin "12") (pinfunction "12_12") (pintype "passive"))
    )
    (net (code "67") (name "unconnected-(JP1-Pad13)") (class "Default")
      (node (ref "JP1") (pin "13") (pinfunction "13_13") (pintype "passive"))
    )
    (net (code "68") (name "unconnected-(JP1-Pad15)") (class "Default")
      (node (ref "JP1") (pin "15") (pinfunction "15_15") (pintype "passive"))
    )
    (net (code "69") (name "unconnected-(JP1-Pad16)") (class "Default")
      (node (ref "JP1") (pin "16") (pinfunction "16_16") (pintype "passive"))
    )
    (net (code "70") (name "unconnected-(JP1-Pad18)") (class "Default")
      (node (ref "JP1") (pin "18") (pinfunction "18_18") (pintype "passive"))
    )
    (net (code "71") (name "unconnected-(JP1-Pad26)") (class "Default")
      (node (ref "JP1") (pin "26") (pinfunction "26_26") (pintype "passive"))
    )
    (net (code "72") (name "unconnected-(JP1-Pad27)") (class "Default")
      (node (ref "JP1") (pin "27") (pinfunction "27_27") (pintype "passive"))
    )
    (net (code "73") (name "unconnected-(JP1-Pad28)") (class "Default")
      (node (ref "JP1") (pin "28") (pinfunction "28_28") (pintype "passive"))
    )
    (net (code "74") (name "unconnected-(JP1-Pad29)") (class "Default")
      (node (ref "JP1") (pin "29") (pinfunction "29_29") (pintype "passive"))
    )
    (net (code "75") (name "unconnected-(JP1-Pad31)") (class "Default")
      (node (ref "JP1") (pin "31") (pinfunction "31_31") (pintype "passive"))
    )
    (net (code "76") (name "unconnected-(JP1-Pad33)") (class "Default")
      (node (ref "JP1") (pin "33") (pinfunction "33_33") (pintype "passive"))
    )
    (net (code "77") (name "unconnected-(JP1-Pad35)") (class "Default")
      (node (ref "JP1") (pin "35") (pinfunction "35_35") (pintype "passive"))
    )
    (net (code "78") (name "unconnected-(JP1-Pad37)") (class "Default")
      (node (ref "JP1") (pin "37") (pinfunction "37_37") (pintype "passive"))
    )
    (net (code "79") (name "unconnected-(JP1-Pad38)") (class "Default")
      (node (ref "JP1") (pin "38") (pinfunction "38_38") (pintype "passive"))
    )
    (net (code "80") (name "unconnected-(JP1-Pad40)") (class "Default")
      (node (ref "JP1") (pin "40") (pinfunction "40_40") (pintype "passive"))
    )
    (net (code "81") (name "unconnected-(U$9-9_LPSTB-Pad9)") (class "Default")
      (node (ref "U$9") (pin "9") (pinfunction "9_LPSTB_9") (pintype "bidirectional"))
    )
  )
)
